# 05_IO_CONN.net
KiCad netlist of a schematic drawn in Altium Designer
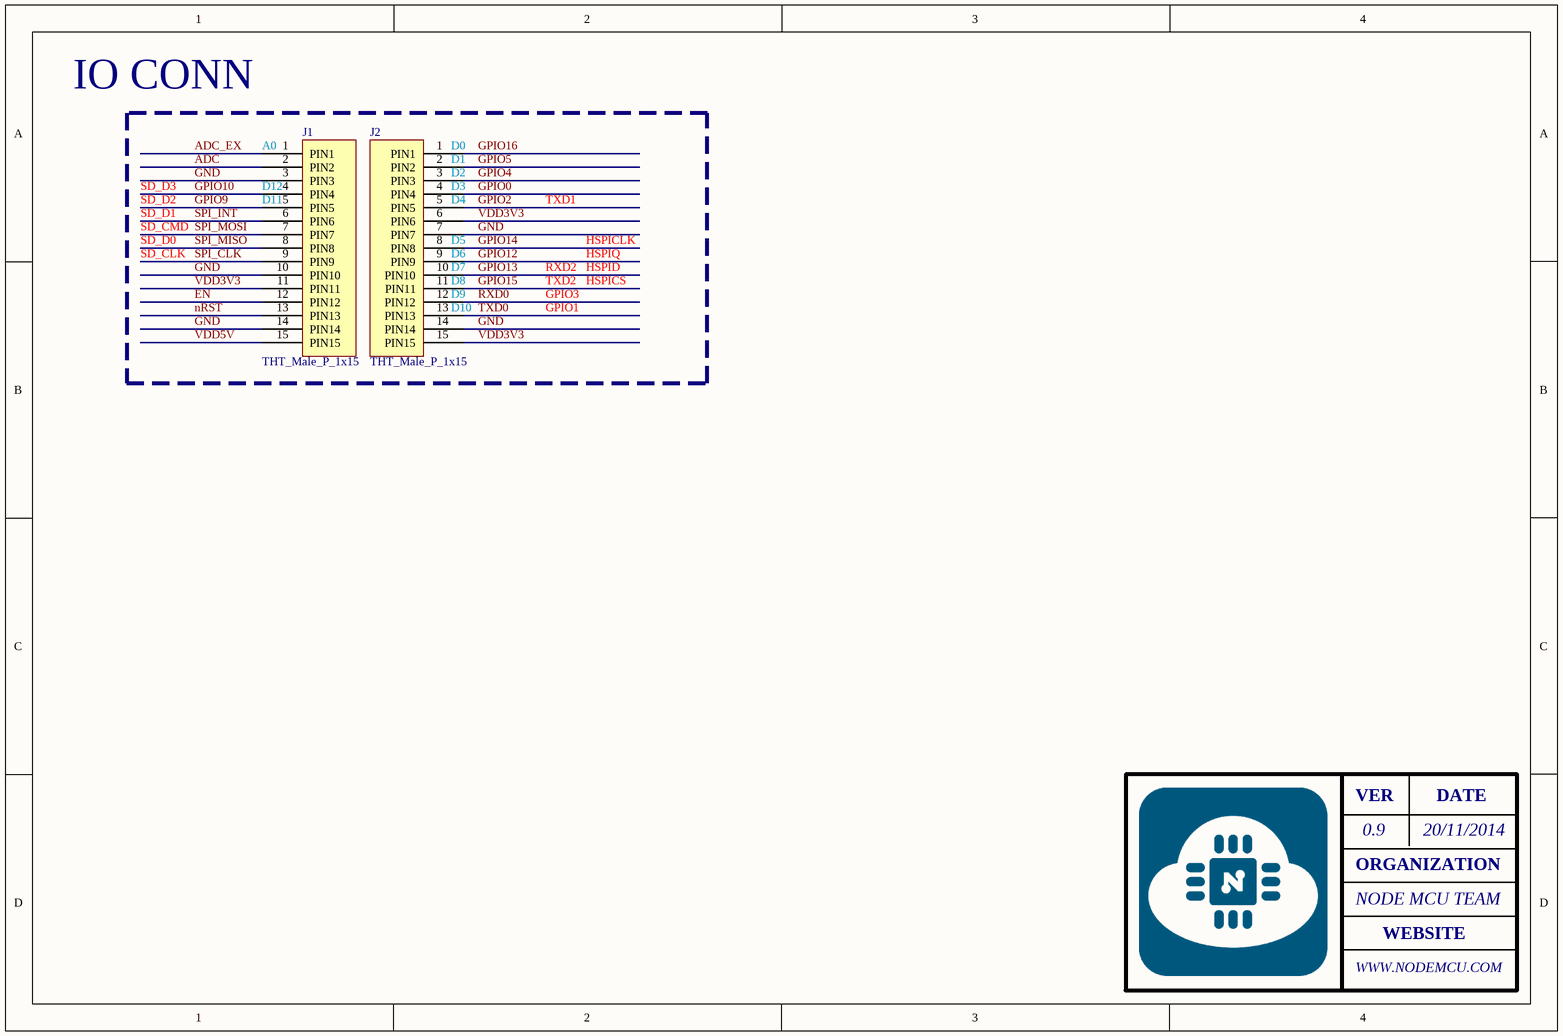
[diagram p0: 05_IO_CONN.SchDoc]

(export (version "E")
  (design (tool "Eeschema 10.0.6"))
  (components
    (comp (ref "J1")
      (value "THT_Male_P_1x15")
      (footprint "THT_Male_P_1x15-2.54mm")
      (description "THT Male pin header strip 1x15")
      (libsource (lib "") (part "THT_Male_P_1x15_1"))
    )
    (comp (ref "J2")
      (value "THT_Male_P_1x15")
      (footprint "THT_Male_P_1x15-2.54mm")
      (description "THT Male pin header strip 1x15")
      (libsource (lib "Vowstar_Connector") (part "THT_Male_P_1x15"))
    )
  )
  (nets
    (net (code "1") (name "/ADC") (class "Default")
      (node (ref "J1") (pin "2") (pinfunction "PIN2_2") (pintype "passive"))
    )
    (net (code "2") (name "/ADC_EX") (class "Default")
      (node (ref "J1") (pin "1") (pinfunction "PIN1_1") (pintype "passive"))
    )
    (net (code "3") (name "/EN") (class "Default")
      (node (ref "J1") (pin "12") (pinfunction "PIN12_12") (pintype "passive"))
    )
    (net (code "4") (name "/GND") (class "Default")
      (node (ref "J1") (pin "10") (pinfunction "PIN10_10") (pintype "passive"))
      (node (ref "J1") (pin "14") (pinfunction "PIN14_14") (pintype "passive"))
      (node (ref "J1") (pin "3") (pinfunction "PIN3_3") (pintype "passive"))
      (node (ref "J2") (pin "14") (pinfunction "PIN14_14") (pintype "passive"))
      (node (ref "J2") (pin "7") (pinfunction "PIN7_7") (pintype "passive"))
    )
    (net (code "5") (name "/GPIO0") (class "Default")
      (node (ref "J2") (pin "4") (pinfunction "PIN4_4") (pintype "passive"))
    )
    (net (code "6") (name "/GPIO2") (class "Default")
      (node (ref "J2") (pin "5") (pinfunction "PIN5_5") (pintype "passive"))
    )
    (net (code "7") (name "/GPIO4") (class "Default")
      (node (ref "J2") (pin "3") (pinfunction "PIN3_3") (pintype "passive"))
    )
    (net (code "8") (name "/GPIO5") (class "Default")
      (node (ref "J2") (pin "2") (pinfunction "PIN2_2") (pintype "passive"))
    )
    (net (code "9") (name "/GPIO9") (class "Default")
      (node (ref "J1") (pin "5") (pinfunction "PIN5_5") (pintype "passive"))
    )
    (net (code "10") (name "/GPIO10") (class "Default")
      (node (ref "J1") (pin "4") (pinfunction "PIN4_4") (pintype "passive"))
    )
    (net (code "11") (name "/GPIO12") (class "Default")
      (node (ref "J2") (pin "9") (pinfunction "PIN9_9") (pintype "passive"))
    )
    (net (code "12") (name "/GPIO13") (class "Default")
      (node (ref "J2") (pin "10") (pinfunction "PIN10_10") (pintype "passive"))
    )
    (net (code "13") (name "/GPIO14") (class "Default")
      (node (ref "J2") (pin "8") (pinfunction "PIN8_8") (pintype "passive"))
    )
    (net (code "14") (name "/GPIO15") (class "Default")
      (node (ref "J2") (pin "11") (pinfunction "PIN11_11") (pintype "passive"))
    )
    (net (code "15") (name "/GPIO16") (class "Default")
      (node (ref "J2") (pin "1") (pinfunction "PIN1_1") (pintype "passive"))
    )
    (net (code "16") (name "/RXD0") (class "Default")
      (node (ref "J2") (pin "12") (pinfunction "PIN12_12") (pintype "passive"))
    )
    (net (code "17") (name "/SPI_CLK") (class "Default")
      (node (ref "J1") (pin "9") (pinfunction "PIN9_9") (pintype "passive"))
    )
    (net (code "18") (name "/SPI_INT") (class "Default")
      (node (ref "J1") (pin "6") (pinfunction "PIN6_6") (pintype "passive"))
    )
    (net (code "19") (name "/SPI_MISO") (class "Default")
      (node (ref "J1") (pin "8") (pinfunction "PIN8_8") (pintype "passive"))
    )
    (net (code "20") (name "/SPI_MOSI") (class "Default")
      (node (ref "J1") (pin "7") (pinfunction "PIN7_7") (pintype "passive"))
    )
    (net (code "21") (name "/TXD0") (class "Default")
      (node (ref "J2") (pin "13") (pinfunction "PIN13_13") (pintype "passive"))
    )
    (net (code "22") (name "/VDD3V3") (class "Default")
      (node (ref "J1") (pin "11") (pinfunction "PIN11_11") (pintype "passive"))
      (node (ref "J2") (pin "15") (pinfunction "PIN15_15") (pintype "passive"))
      (node (ref "J2") (pin "6") (pinfunction "PIN6_6") (pintype "passive"))
    )
    (net (code "23") (name "/VDD5V") (class "Default")
      (node (ref "J1") (pin "15") (pinfunction "PIN15_15") (pintype "passive"))
    )
    (net (code "24") (name "/nRST") (class "Default")
      (node (ref "J1") (pin "13") (pinfunction "PIN13_13") (pintype "passive"))
    )
  )
)
